# 02_ESP32_MAIN_B.net
KiCad netlist of a schematic drawn in Altium Designer
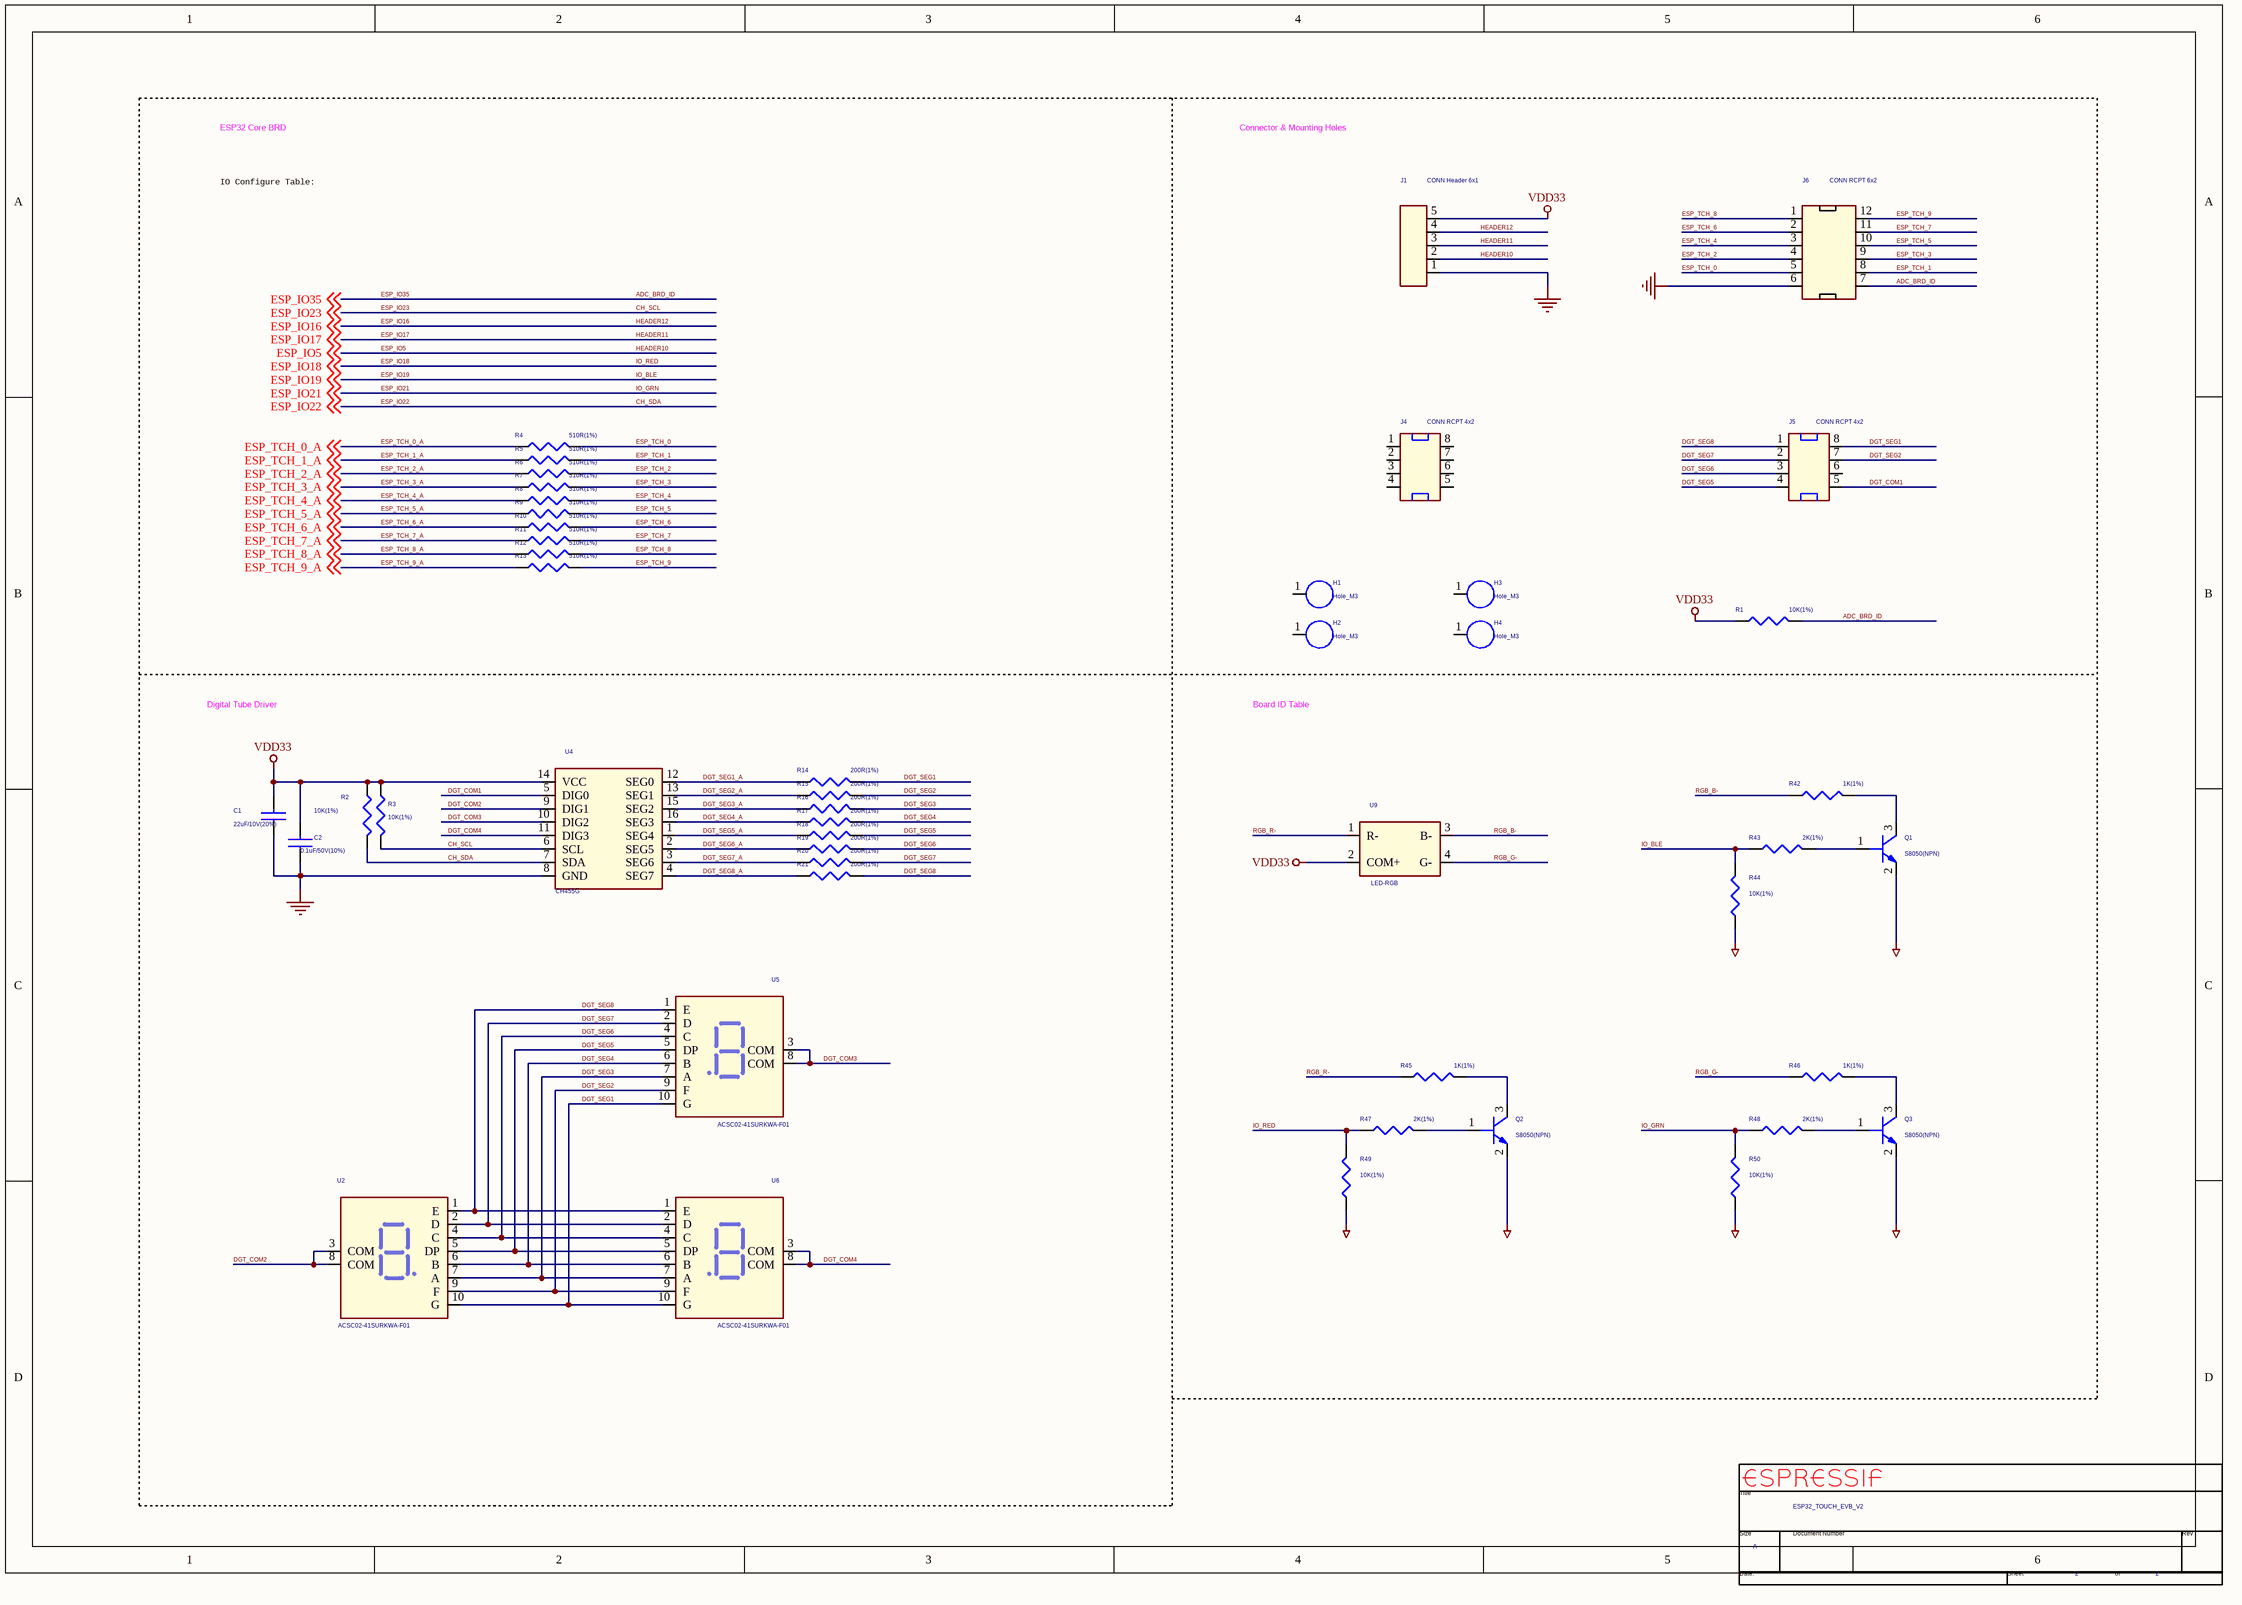
[diagram p0: 02 ESP32 MAIN_B.SchDoc]

(export (version "E")
  (design (tool "Eeschema 10.0.6"))
  (components
    (comp (ref "C1") (value "22uF/10V(20%)") (footprint "0603C") (libsource (lib "*") (part "CAP NP")))
    (comp (ref "C2") (value "0.1uF/50V(10%)") (footprint "0402C") (libsource (lib "*") (part "CAP NP")))
    (comp (ref "H1") (value "Hole_M3") (footprint "MTGH200C125D-N") (libsource (lib "*") (part "CON1_0")))
    (comp (ref "H2") (value "Hole_M3") (footprint "MTGH200C125D-N") (libsource (lib "*") (part "CON1_0")))
    (comp (ref "H3") (value "Hole_M3") (footprint "MTGH200C125D-N") (libsource (lib "*") (part "CON1_0")))
    (comp (ref "H4") (value "Hole_M3") (footprint "MTGH200C125D-N") (libsource (lib "*") (part "CON1_0")))
    (comp (ref "J1")
      (value "CONN Header 6x1")
      (footprint "CON_5x1_2P54")
      (libsource (lib "*") (part "12 HEADER_12"))
    )
    (comp (ref "J4")
      (value "CONN RCPT 4x2")
      (footprint "CON_F_4x2_2P00")
      (libsource (lib "*") (part "12 HEADER_5"))
    )
    (comp (ref "J5")
      (value "CONN RCPT 4x2")
      (footprint "CON_F_4x2_2P00")
      (libsource (lib "*") (part "12 HEADER_5"))
    )
    (comp (ref "J6")
      (value "CONN RCPT 6x2")
      (footprint "CON_F_6x2_2P00")
      (libsource (lib "*") (part "CONN RCPT 10x2_2"))
    )
    (comp (ref "Q1") (value "S8050(NPN)") (footprint "SOT-23-3") (libsource (lib "*") (part "NPN BCE_0")))
    (comp (ref "Q2") (value "S8050(NPN)") (footprint "SOT-23-3") (libsource (lib "*") (part "NPN BCE_0")))
    (comp (ref "Q3") (value "S8050(NPN)") (footprint "SOT-23-3") (libsource (lib "*") (part "NPN BCE_0")))
    (comp (ref "R1") (value "10K(1%)") (footprint "0402R") (libsource (lib "*") (part "RESISTOR")))
    (comp (ref "R2") (value "10K(1%)") (footprint "0402R") (libsource (lib "*") (part "RESISTOR_0")))
    (comp (ref "R3") (value "10K(1%)") (footprint "0402R") (libsource (lib "*") (part "RESISTOR_0")))
    (comp (ref "R4") (value "510R(1%)") (footprint "0402R") (libsource (lib "*") (part "RESISTOR")))
    (comp (ref "R5") (value "510R(1%)") (footprint "0402R") (libsource (lib "*") (part "RESISTOR")))
    (comp (ref "R6") (value "510R(1%)") (footprint "0402R") (libsource (lib "*") (part "RESISTOR")))
    (comp (ref "R7") (value "510R(1%)") (footprint "0402R") (libsource (lib "*") (part "RESISTOR")))
    (comp (ref "R8") (value "510R(1%)") (footprint "0402R") (libsource (lib "*") (part "RESISTOR")))
    (comp (ref "R9") (value "510R(1%)") (footprint "0402R") (libsource (lib "*") (part "RESISTOR")))
    (comp (ref "R10") (value "510R(1%)") (footprint "0402R") (libsource (lib "*") (part "RESISTOR")))
    (comp (ref "R11") (value "510R(1%)") (footprint "0402R") (libsource (lib "*") (part "RESISTOR")))
    (comp (ref "R12") (value "510R(1%)") (footprint "0402R") (libsource (lib "*") (part "RESISTOR")))
    (comp (ref "R13") (value "510R(1%)") (footprint "0402R") (libsource (lib "*") (part "RESISTOR")))
    (comp (ref "R14") (value "200R(1%)") (footprint "0402R") (libsource (lib "*") (part "RESISTOR")))
    (comp (ref "R15") (value "200R(1%)") (footprint "0402R") (libsource (lib "*") (part "RESISTOR")))
    (comp (ref "R16") (value "200R(1%)") (footprint "0402R") (libsource (lib "*") (part "RESISTOR")))
    (comp (ref "R17") (value "200R(1%)") (footprint "0402R") (libsource (lib "*") (part "RESISTOR")))
    (comp (ref "R18") (value "200R(1%)") (footprint "0402R") (libsource (lib "*") (part "RESISTOR")))
    (comp (ref "R19") (value "200R(1%)") (footprint "0402R") (libsource (lib "*") (part "RESISTOR")))
    (comp (ref "R20") (value "200R(1%)") (footprint "0402R") (libsource (lib "*") (part "RESISTOR")))
    (comp (ref "R21") (value "200R(1%)") (footprint "0402R") (libsource (lib "*") (part "RESISTOR")))
    (comp (ref "R42") (value "1K(1%)") (footprint "0402R") (libsource (lib "*") (part "RESISTOR_0")))
    (comp (ref "R43") (value "2K(1%)") (footprint "0402R") (libsource (lib "*") (part "RESISTOR")))
    (comp (ref "R44") (value "10K(1%)") (footprint "0402R") (libsource (lib "*") (part "RESISTOR_0")))
    (comp (ref "R45") (value "1K(1%)") (footprint "0402R") (libsource (lib "*") (part "RESISTOR_0")))
    (comp (ref "R46") (value "1K(1%)") (footprint "0402R") (libsource (lib "*") (part "RESISTOR_0")))
    (comp (ref "R47") (value "2K(1%)") (footprint "0402R") (libsource (lib "*") (part "RESISTOR")))
    (comp (ref "R48") (value "2K(1%)") (footprint "0402R") (libsource (lib "*") (part "RESISTOR")))
    (comp (ref "R49") (value "10K(1%)") (footprint "0402R") (libsource (lib "*") (part "RESISTOR_0")))
    (comp (ref "R50") (value "10K(1%)") (footprint "0402R") (libsource (lib "*") (part "RESISTOR_0")))
    (comp (ref "U2")
      (value "ACSC02-41SURKWA-F01")
      (footprint "DG10069")
      (libsource (lib "") (part "Digital_Tube_1"))
    )
    (comp (ref "U4") (value "CH455G") (footprint "SOP16-150MIL") (libsource (lib "*") (part "74HC138_4")))
    (comp (ref "U5")
      (value "ACSC02-41SURKWA-F01")
      (footprint "DG10069")
      (libsource (lib "*") (part "Digital_Tube"))
    )
    (comp (ref "U6")
      (value "ACSC02-41SURKWA-F01")
      (footprint "DG10069")
      (libsource (lib "*") (part "Digital_Tube"))
    )
    (comp (ref "U9") (value "LED-RGB") (footprint "LED3528") (libsource (lib "*") (part "LED-RGB")))
  )
  (nets
    (net (code "1") (name "/DGT_COM1") (class "Default")
      (node (ref "J5") (pin "5") (pinfunction "5_5") (pintype "passive"))
      (node (ref "U4") (pin "5") (pinfunction "DIG0_5") (pintype "passive"))
    )
    (net (code "2") (name "/DGT_COM2") (class "Default")
      (node (ref "U2") (pin "3") (pinfunction "COM_3") (pintype "passive"))
      (node (ref "U2") (pin "8") (pinfunction "COM_8") (pintype "passive"))
      (node (ref "U4") (pin "9") (pinfunction "DIG1_9") (pintype "passive"))
    )
    (net (code "3") (name "/DGT_COM3") (class "Default")
      (node (ref "U4") (pin "10") (pinfunction "DIG2_10") (pintype "passive"))
      (node (ref "U5") (pin "3") (pinfunction "COM_3") (pintype "passive"))
      (node (ref "U5") (pin "8") (pinfunction "COM_8") (pintype "passive"))
    )
    (net (code "4") (name "/DGT_COM4") (class "Default")
      (node (ref "U4") (pin "11") (pinfunction "DIG3_11") (pintype "passive"))
      (node (ref "U6") (pin "3") (pinfunction "COM_3") (pintype "passive"))
      (node (ref "U6") (pin "8") (pinfunction "COM_8") (pintype "passive"))
    )
    (net (code "5") (name "/DGT_SEG1") (class "Default")
      (node (ref "J5") (pin "8") (pinfunction "8_8") (pintype "passive"))
      (node (ref "R14") (pin "2") (pinfunction "2_2") (pintype "passive"))
      (node (ref "U2") (pin "10") (pinfunction "G_10") (pintype "passive"))
      (node (ref "U5") (pin "10") (pinfunction "G_10") (pintype "passive"))
      (node (ref "U6") (pin "10") (pinfunction "G_10") (pintype "passive"))
    )
    (net (code "6") (name "/DGT_SEG1_A") (class "Default")
      (node (ref "R14") (pin "1") (pinfunction "1_1") (pintype "passive"))
      (node (ref "U4") (pin "12") (pinfunction "SEG0_12") (pintype "passive"))
    )
    (net (code "7") (name "/DGT_SEG2") (class "Default")
      (node (ref "J5") (pin "7") (pinfunction "7_7") (pintype "passive"))
      (node (ref "R15") (pin "2") (pinfunction "2_2") (pintype "passive"))
      (node (ref "U2") (pin "9") (pinfunction "F_9") (pintype "passive"))
      (node (ref "U5") (pin "9") (pinfunction "F_9") (pintype "passive"))
      (node (ref "U6") (pin "9") (pinfunction "F_9") (pintype "passive"))
    )
    (net (code "8") (name "/DGT_SEG2_A") (class "Default")
      (node (ref "R15") (pin "1") (pinfunction "1_1") (pintype "passive"))
      (node (ref "U4") (pin "13") (pinfunction "SEG1_13") (pintype "passive"))
    )
    (net (code "9") (name "/DGT_SEG3") (class "Default")
      (node (ref "R16") (pin "2") (pinfunction "2_2") (pintype "passive"))
      (node (ref "U2") (pin "7") (pinfunction "A_7") (pintype "passive"))
      (node (ref "U5") (pin "7") (pinfunction "A_7") (pintype "passive"))
      (node (ref "U6") (pin "7") (pinfunction "A_7") (pintype "passive"))
    )
    (net (code "10") (name "/DGT_SEG3_A") (class "Default")
      (node (ref "R16") (pin "1") (pinfunction "1_1") (pintype "passive"))
      (node (ref "U4") (pin "15") (pinfunction "SEG2_15") (pintype "passive"))
    )
    (net (code "11") (name "/DGT_SEG4") (class "Default")
      (node (ref "R17") (pin "2") (pinfunction "2_2") (pintype "passive"))
      (node (ref "U2") (pin "6") (pinfunction "B_6") (pintype "passive"))
      (node (ref "U5") (pin "6") (pinfunction "B_6") (pintype "passive"))
      (node (ref "U6") (pin "6") (pinfunction "B_6") (pintype "passive"))
    )
    (net (code "12") (name "/DGT_SEG4_A") (class "Default")
      (node (ref "R17") (pin "1") (pinfunction "1_1") (pintype "passive"))
      (node (ref "U4") (pin "16") (pinfunction "SEG3_16") (pintype "passive"))
    )
    (net (code "13") (name "/DGT_SEG5") (class "Default")
      (node (ref "J5") (pin "4") (pinfunction "4_4") (pintype "passive"))
      (node (ref "R18") (pin "2") (pinfunction "2_2") (pintype "passive"))
      (node (ref "U2") (pin "5") (pinfunction "DP_5") (pintype "passive"))
      (node (ref "U5") (pin "5") (pinfunction "DP_5") (pintype "passive"))
      (node (ref "U6") (pin "5") (pinfunction "DP_5") (pintype "passive"))
    )
    (net (code "14") (name "/DGT_SEG5_A") (class "Default")
      (node (ref "R18") (pin "1") (pinfunction "1_1") (pintype "passive"))
      (node (ref "U4") (pin "1") (pinfunction "SEG4_1") (pintype "passive"))
    )
    (net (code "15") (name "/DGT_SEG6") (class "Default")
      (node (ref "J5") (pin "3") (pinfunction "3_3") (pintype "passive"))
      (node (ref "R19") (pin "2") (pinfunction "2_2") (pintype "passive"))
      (node (ref "U2") (pin "4") (pinfunction "C_4") (pintype "passive"))
      (node (ref "U5") (pin "4") (pinfunction "C_4") (pintype "passive"))
      (node (ref "U6") (pin "4") (pinfunction "C_4") (pintype "passive"))
    )
    (net (code "16") (name "/DGT_SEG6_A") (class "Default")
      (node (ref "R19") (pin "1") (pinfunction "1_1") (pintype "passive"))
      (node (ref "U4") (pin "2") (pinfunction "SEG5_2") (pintype "passive"))
    )
    (net (code "17") (name "/DGT_SEG7") (class "Default")
      (node (ref "J5") (pin "2") (pinfunction "2_2") (pintype "passive"))
      (node (ref "R20") (pin "2") (pinfunction "2_2") (pintype "passive"))
      (node (ref "U2") (pin "2") (pinfunction "D_2") (pintype "passive"))
      (node (ref "U5") (pin "2") (pinfunction "D_2") (pintype "passive"))
      (node (ref "U6") (pin "2") (pinfunction "D_2") (pintype "passive"))
    )
    (net (code "18") (name "/DGT_SEG7_A") (class "Default")
      (node (ref "R20") (pin "1") (pinfunction "1_1") (pintype "passive"))
      (node (ref "U4") (pin "3") (pinfunction "SEG6_3") (pintype "passive"))
    )
    (net (code "19") (name "/DGT_SEG8") (class "Default")
      (node (ref "J5") (pin "1") (pinfunction "1_1") (pintype "passive"))
      (node (ref "R21") (pin "2") (pinfunction "2_2") (pintype "passive"))
      (node (ref "U2") (pin "1") (pinfunction "E_1") (pintype "passive"))
      (node (ref "U5") (pin "1") (pinfunction "E_1") (pintype "passive"))
      (node (ref "U6") (pin "1") (pinfunction "E_1") (pintype "passive"))
    )
    (net (code "20") (name "/DGT_SEG8_A") (class "Default")
      (node (ref "R21") (pin "1") (pinfunction "1_1") (pintype "passive"))
      (node (ref "U4") (pin "4") (pinfunction "SEG7_4") (pintype "passive"))
    )
    (net (code "21") (name "/ESP_TCH_0") (class "Default")
      (node (ref "J6") (pin "5") (pinfunction "5_5") (pintype "passive"))
      (node (ref "R4") (pin "2") (pinfunction "2_2") (pintype "passive"))
    )
    (net (code "22") (name "/ESP_TCH_1") (class "Default")
      (node (ref "J6") (pin "8") (pinfunction "8_8") (pintype "passive"))
      (node (ref "R5") (pin "2") (pinfunction "2_2") (pintype "passive"))
    )
    (net (code "23") (name "/ESP_TCH_2") (class "Default")
      (node (ref "J6") (pin "4") (pinfunction "4_4") (pintype "passive"))
      (node (ref "R6") (pin "2") (pinfunction "2_2") (pintype "passive"))
    )
    (net (code "24") (name "/ESP_TCH_3") (class "Default")
      (node (ref "J6") (pin "9") (pinfunction "9_9") (pintype "passive"))
      (node (ref "R7") (pin "2") (pinfunction "2_2") (pintype "passive"))
    )
    (net (code "25") (name "/ESP_TCH_4") (class "Default")
      (node (ref "J6") (pin "3") (pinfunction "3_3") (pintype "passive"))
      (node (ref "R8") (pin "2") (pinfunction "2_2") (pintype "passive"))
    )
    (net (code "26") (name "/ESP_TCH_5") (class "Default")
      (node (ref "J6") (pin "10") (pinfunction "10_10") (pintype "passive"))
      (node (ref "R9") (pin "2") (pinfunction "2_2") (pintype "passive"))
    )
    (net (code "27") (name "/ESP_TCH_6") (class "Default")
      (node (ref "J6") (pin "2") (pinfunction "2_2") (pintype "passive"))
      (node (ref "R10") (pin "2") (pinfunction "2_2") (pintype "passive"))
    )
    (net (code "28") (name "/ESP_TCH_7") (class "Default")
      (node (ref "J6") (pin "11") (pinfunction "11_11") (pintype "passive"))
      (node (ref "R11") (pin "2") (pinfunction "2_2") (pintype "passive"))
    )
    (net (code "29") (name "/ESP_TCH_8") (class "Default")
      (node (ref "J6") (pin "1") (pinfunction "1_1") (pintype "passive"))
      (node (ref "R12") (pin "2") (pinfunction "2_2") (pintype "passive"))
    )
    (net (code "30") (name "/ESP_TCH_9") (class "Default")
      (node (ref "J6") (pin "12") (pinfunction "12_12") (pintype "passive"))
      (node (ref "R13") (pin "2") (pinfunction "2_2") (pintype "passive"))
    )
    (net (code "31") (name "/RGB_B-") (class "Default")
      (node (ref "R42") (pin "1") (pinfunction "1_1") (pintype "passive"))
      (node (ref "U9") (pin "3") (pinfunction "B-_3") (pintype "passive"))
    )
    (net (code "32") (name "/RGB_G-") (class "Default")
      (node (ref "R46") (pin "1") (pinfunction "1_1") (pintype "passive"))
      (node (ref "U9") (pin "4") (pinfunction "G-_4") (pintype "passive"))
    )
    (net (code "33") (name "/RGB_R-") (class "Default")
      (node (ref "R45") (pin "1") (pinfunction "1_1") (pintype "passive"))
      (node (ref "U9") (pin "1") (pinfunction "R-_1") (pintype "passive"))
    )
    (net (code "34") (name "ESP_IO5") (class "Default")
      (node (ref "J1") (pin "2") (pinfunction "2_2") (pintype "passive"))
    )
    (net (code "35") (name "ESP_IO16") (class "Default")
      (node (ref "J1") (pin "4") (pinfunction "4_4") (pintype "passive"))
    )
    (net (code "36") (name "ESP_IO17") (class "Default")
      (node (ref "J1") (pin "3") (pinfunction "3_3") (pintype "passive"))
    )
    (net (code "37") (name "ESP_IO18") (class "Default")
      (node (ref "R47") (pin "1") (pinfunction "1_1") (pintype "passive"))
      (node (ref "R49") (pin "2") (pinfunction "2_2") (pintype "passive"))
    )
    (net (code "38") (name "ESP_IO19") (class "Default")
      (node (ref "R43") (pin "1") (pinfunction "1_1") (pintype "passive"))
      (node (ref "R44") (pin "2") (pinfunction "2_2") (pintype "passive"))
    )
    (net (code "39") (name "ESP_IO21") (class "Default")
      (node (ref "R48") (pin "1") (pinfunction "1_1") (pintype "passive"))
      (node (ref "R50") (pin "2") (pinfunction "2_2") (pintype "passive"))
    )
    (net (code "40") (name "ESP_IO22") (class "Default")
      (node (ref "R2") (pin "2") (pinfunction "2_2") (pintype "passive"))
      (node (ref "U4") (pin "7") (pinfunction "SDA_7") (pintype "passive"))
    )
    (net (code "41") (name "ESP_IO23") (class "Default")
      (node (ref "R3") (pin "2") (pinfunction "2_2") (pintype "passive"))
      (node (ref "U4") (pin "6") (pinfunction "SCL_6") (pintype "passive"))
    )
    (net (code "42") (name "ESP_IO35") (class "Default")
      (node (ref "J6") (pin "7") (pinfunction "7_7") (pintype "passive"))
      (node (ref "R1") (pin "2") (pinfunction "2_2") (pintype "passive"))
    )
    (net (code "43") (name "ESP_TCH_0_A") (class "Default")
      (node (ref "R4") (pin "1") (pinfunction "1_1") (pintype "passive"))
    )
    (net (code "44") (name "ESP_TCH_1_A") (class "Default")
      (node (ref "R5") (pin "1") (pinfunction "1_1") (pintype "passive"))
    )
    (net (code "45") (name "ESP_TCH_2_A") (class "Default")
      (node (ref "R6") (pin "1") (pinfunction "1_1") (pintype "passive"))
    )
    (net (code "46") (name "ESP_TCH_3_A") (class "Default")
      (node (ref "R7") (pin "1") (pinfunction "1_1") (pintype "passive"))
    )
    (net (code "47") (name "ESP_TCH_4_A") (class "Default")
      (node (ref "R8") (pin "1") (pinfunction "1_1") (pintype "passive"))
    )
    (net (code "48") (name "ESP_TCH_5_A") (class "Default")
      (node (ref "R9") (pin "1") (pinfunction "1_1") (pintype "passive"))
    )
    (net (code "49") (name "ESP_TCH_6_A") (class "Default")
      (node (ref "R10") (pin "1") (pinfunction "1_1") (pintype "passive"))
    )
    (net (code "50") (name "ESP_TCH_7_A") (class "Default")
      (node (ref "R11") (pin "1") (pinfunction "1_1") (pintype "passive"))
    )
    (net (code "51") (name "ESP_TCH_8_A") (class "Default")
      (node (ref "R12") (pin "1") (pinfunction "1_1") (pintype "passive"))
    )
    (net (code "52") (name "ESP_TCH_9_A") (class "Default")
      (node (ref "R13") (pin "1") (pinfunction "1_1") (pintype "passive"))
    )
    (net (code "53") (name "GND") (class "Default")
      (node (ref "C1") (pin "1") (pinfunction "1_1") (pintype "passive"))
      (node (ref "C2") (pin "1") (pinfunction "1_1") (pintype "passive"))
      (node (ref "J1") (pin "1") (pinfunction "1_1") (pintype "passive"))
      (node (ref "J6") (pin "6") (pinfunction "6_6") (pintype "passive"))
      (node (ref "Q1") (pin "2") (pinfunction "E_2") (pintype "passive"))
      (node (ref "Q2") (pin "2") (pinfunction "E_2") (pintype "passive"))
      (node (ref "Q3") (pin "2") (pinfunction "E_2") (pintype "passive"))
      (node (ref "R44") (pin "1") (pinfunction "1_1") (pintype "passive"))
      (node (ref "R49") (pin "1") (pinfunction "1_1") (pintype "passive"))
      (node (ref "R50") (pin "1") (pinfunction "1_1") (pintype "passive"))
      (node (ref "U4") (pin "8") (pinfunction "GND_8") (pintype "passive"))
    )
    (net (code "54") (name "Net-(Q1-B)") (class "Default")
      (node (ref "Q1") (pin "1") (pinfunction "B_1") (pintype "passive"))
      (node (ref "R43") (pin "2") (pinfunction "2_2") (pintype "passive"))
    )
    (net (code "55") (name "Net-(Q1-C)") (class "Default")
      (node (ref "Q1") (pin "3") (pinfunction "C_3") (pintype "passive"))
      (node (ref "R42") (pin "2") (pinfunction "2_2") (pintype "passive"))
    )
    (net (code "56") (name "Net-(Q2-B)") (class "Default")
      (node (ref "Q2") (pin "1") (pinfunction "B_1") (pintype "passive"))
      (node (ref "R47") (pin "2") (pinfunction "2_2") (pintype "passive"))
    )
    (net (code "57") (name "Net-(Q2-C)") (class "Default")
      (node (ref "Q2") (pin "3") (pinfunction "C_3") (pintype "passive"))
      (node (ref "R45") (pin "2") (pinfunction "2_2") (pintype "passive"))
    )
    (net (code "58") (name "Net-(Q3-B)") (class "Default")
      (node (ref "Q3") (pin "1") (pinfunction "B_1") (pintype "passive"))
      (node (ref "R48") (pin "2") (pinfunction "2_2") (pintype "passive"))
    )
    (net (code "59") (name "Net-(Q3-C)") (class "Default")
      (node (ref "Q3") (pin "3") (pinfunction "C_3") (pintype "passive"))
      (node (ref "R46") (pin "2") (pinfunction "2_2") (pintype "passive"))
    )
    (net (code "60") (name "VDD33") (class "Default")
      (node (ref "C1") (pin "2") (pinfunction "2_2") (pintype "passive"))
      (node (ref "C2") (pin "2") (pinfunction "2_2") (pintype "passive"))
      (node (ref "J1") (pin "5") (pinfunction "5_5") (pintype "passive"))
      (node (ref "R1") (pin "1") (pinfunction "1_1") (pintype "passive"))
      (node (ref "R2") (pin "1") (pinfunction "1_1") (pintype "passive"))
      (node (ref "R3") (pin "1") (pinfunction "1_1") (pintype "passive"))
      (node (ref "U4") (pin "14") (pinfunction "VCC_14") (pintype "passive"))
      (node (ref "U9") (pin "2") (pinfunction "COM+_2") (pintype "passive"))
    )
    (net (code "61") (name "unconnected-(H1-Pad1)") (class "Default")
      (node (ref "H1") (pin "1") (pinfunction "1_1") (pintype "passive"))
    )
    (net (code "62") (name "unconnected-(H2-Pad1)") (class "Default")
      (node (ref "H2") (pin "1") (pinfunction "1_1") (pintype "passive"))
    )
    (net (code "63") (name "unconnected-(H3-Pad1)") (class "Default")
      (node (ref "H3") (pin "1") (pinfunction "1_1") (pintype "passive"))
    )
    (net (code "64") (name "unconnected-(H4-Pad1)") (class "Default")
      (node (ref "H4") (pin "1") (pinfunction "1_1") (pintype "passive"))
    )
    (net (code "65") (name "unconnected-(J4-Pad1)") (class "Default")
      (node (ref "J4") (pin "1") (pinfunction "1_1") (pintype "passive"))
    )
    (net (code "66") (name "unconnected-(J4-Pad2)") (class "Default")
      (node (ref "J4") (pin "2") (pinfunction "2_2") (pintype "passive"))
    )
    (net (code "67") (name "unconnected-(J4-Pad3)") (class "Default")
      (node (ref "J4") (pin "3") (pinfunction "3_3") (pintype "passive"))
    )
    (net (code "68") (name "unconnected-(J4-Pad4)") (class "Default")
      (node (ref "J4") (pin "4") (pinfunction "4_4") (pintype "passive"))
    )
    (net (code "69") (name "unconnected-(J4-Pad5)") (class "Default")
      (node (ref "J4") (pin "5") (pinfunction "5_5") (pintype "passive"))
    )
    (net (code "70") (name "unconnected-(J4-Pad6)") (class "Default")
      (node (ref "J4") (pin "6") (pinfunction "6_6") (pintype "passive"))
    )
    (net (code "71") (name "unconnected-(J4-Pad7)") (class "Default")
      (node (ref "J4") (pin "7") (pinfunction "7_7") (pintype "passive"))
    )
    (net (code "72") (name "unconnected-(J4-Pad8)") (class "Default")
      (node (ref "J4") (pin "8") (pinfunction "8_8") (pintype "passive"))
    )
    (net (code "73") (name "unconnected-(J5-Pad6)") (class "Default")
      (node (ref "J5") (pin "6") (pinfunction "6_6") (pintype "passive"))
    )
  )
)
